# BEE_BOARD_POWER.net
KiCad netlist of a schematic drawn in Altium Designer
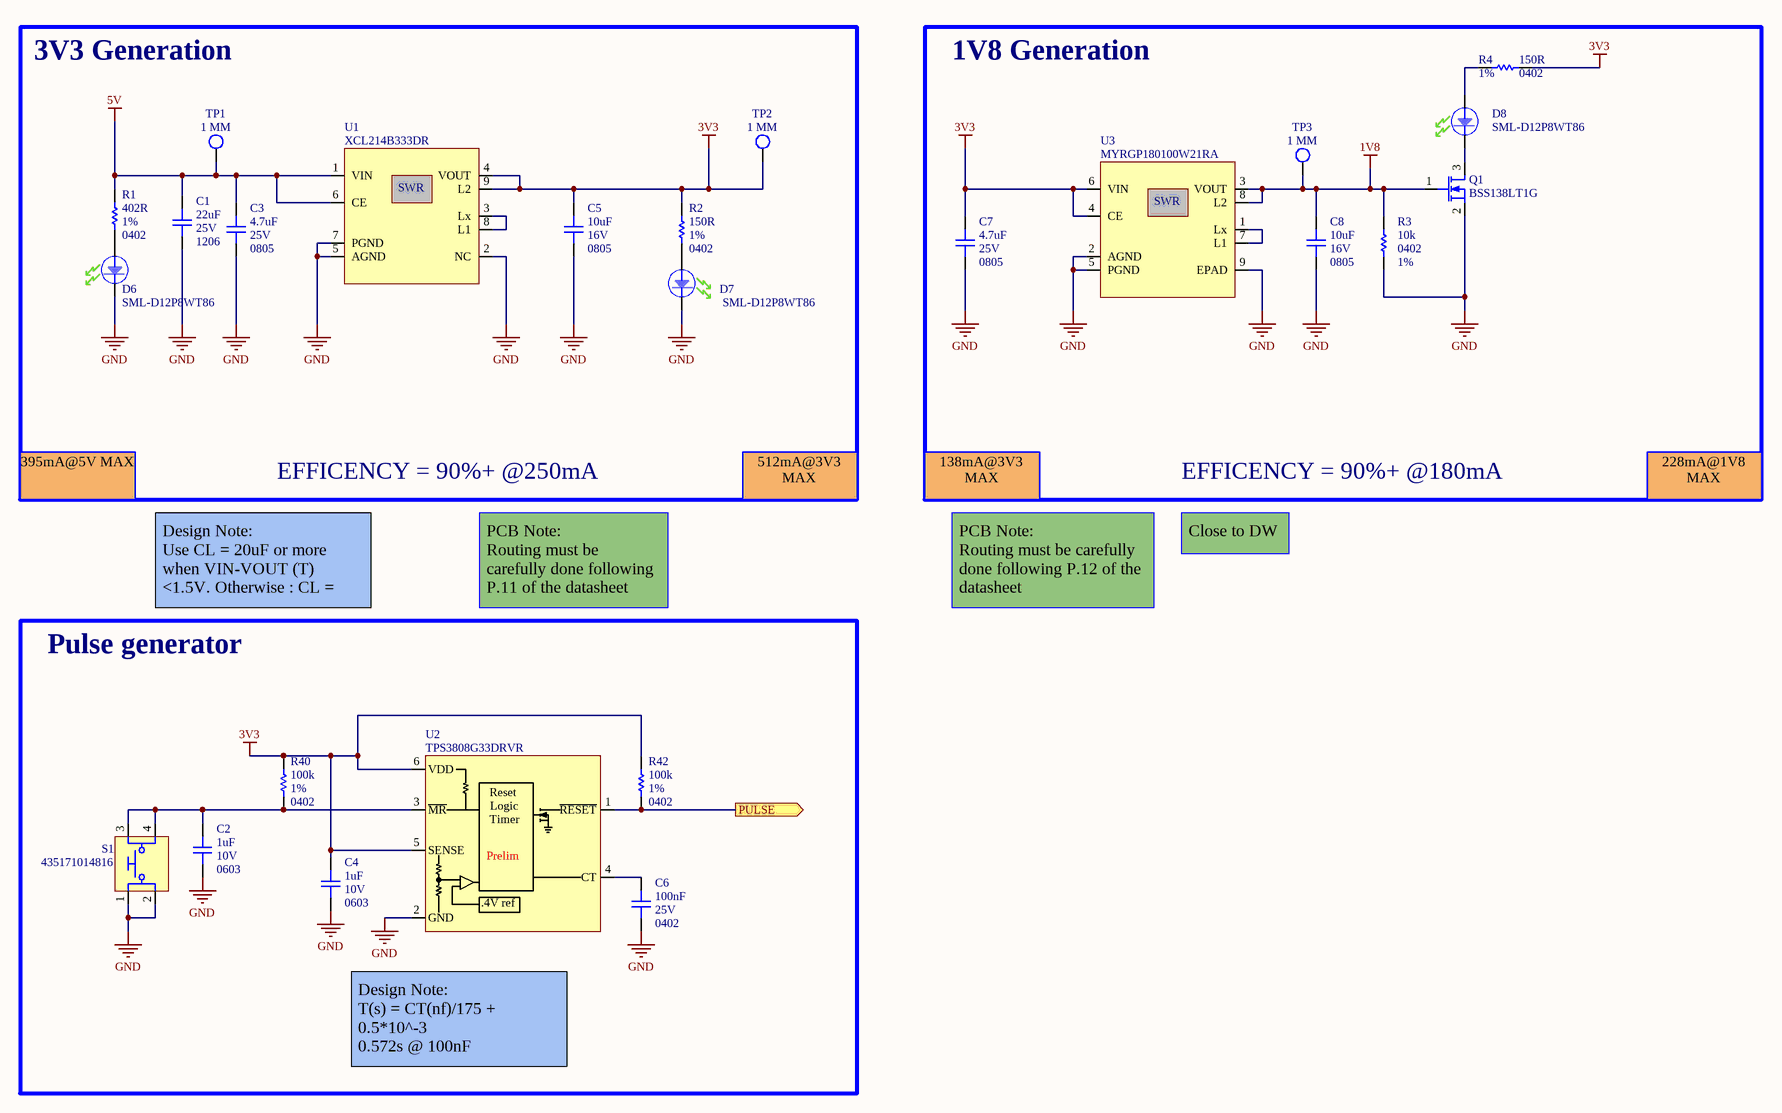
[diagram p0: BEE_BOARD_POWER.SchDoc]

(export (version "E")
  (design (tool "Eeschema 10.0.6"))
  (components
    (comp (ref "C1")
      (value "22uF")
      (footprint "grams_master_lib_pcb:CAP_CER_1206")
      (description "CAP - CER 22uF 10% 25V X5R - 1206")
      (fields
        (field (name "TOLERANCE") "10%")
        (field (name "PACKAGE") "1206")
        (field (name "VOLTAGE RATING") "25V")
        (field (name "Comment") "CL31A226KAHNNNE")
        (field (name "CREATEDBY/DATE") "Philippe Arsenault/21 Janvier 2020")
        (field (name "VERIFIEDBY") "C.Paulin - 28/01/2020")
      )
      (libsource (lib "GRAMS_MASTER_LIB_SCH") (part "CAP_CER_CL31A226KAHNNNE"))
    )
    (comp (ref "C2")
      (value "1uF")
      (footprint "CAP_CER_0603")
      (description "CAP - CER 1uF 10V 10% X5R - 0603")
      (fields
        (field (name "TOLERANCE") "10%")
        (field (name "PACKAGE") "0603")
        (field (name "VOLTAGE RATING") "10V")
        (field (name "Comment") "C0603C105K8PACTU")
        (field (name "CREATEDBY/DATE") "Hubert Dube - 21/07/20")
        (field (name "VERIFIEDBY") "Louis-Daniel Gaulin - 21/07/20")
      )
      (libsource (lib "SWARMUS_LIB") (part "CAP_CER_C0603C105K8PACTU"))
    )
    (comp (ref "C3")
      (value "4.7uF")
      (footprint "GRAMS_MASTER_LIB_PCB:CAP_CER_0805")
      (description "CAP - CER 4.7UF 10% 25V X7R - 0805")
      (fields
        (field (name "TOLERANCE") "10%")
        (field (name "PACKAGE") "0805")
        (field (name "VOLTAGE RATING") "25V")
        (field (name "Comment") "C2012X7R1E475K125AE")
        (field (name "CREATEDBY/DATE") "Keven Deslandes - 2018/11/09")
        (field (name "VERIFIEDBY") "Nicolas Roy - 2018/12/11")
      )
      (libsource (lib "GRAMS_MASTER_LIB_SCH") (part "CAP_CER_C2012X7R1E475K125AE"))
    )
    (comp (ref "C4")
      (value "1uF")
      (footprint "CAP_CER_0603")
      (description "CAP - CER 1uF 10V 10% X5R - 0603")
      (fields
        (field (name "TOLERANCE") "10%")
        (field (name "PACKAGE") "0603")
        (field (name "VOLTAGE RATING") "10V")
        (field (name "Comment") "C0603C105K8PACTU")
        (field (name "CREATEDBY/DATE") "Hubert Dube - 21/07/20")
        (field (name "VERIFIEDBY") "Louis-Daniel Gaulin - 21/07/20")
      )
      (libsource (lib "SWARMUS_LIB") (part "CAP_CER_C0603C105K8PACTU"))
    )
    (comp (ref "C5")
      (value "10uF")
      (footprint "GRAMS_MASTER_LIB_PCB:CAP_CER_0805")
      (description "CAP - CER 10UF 10% 16V X5R - 0805")
      (fields
        (field (name "TOLERANCE") "10%")
        (field (name "PACKAGE") "0805")
        (field (name "VOLTAGE RATING") "16V")
        (field (name "Comment") "GRM21BR61C106KE15K")
        (field (name "CREATEDBY/DATE") "Caroline Paulin / 8 août 2018")
        (field (name "VERIFIEDBY") "Nicolas V. (2019-01-22)")
      )
      (libsource (lib "GRAMS_MASTER_LIB_SCH") (part "CAP_CER_GRM21BR61C106KE15K"))
    )
    (comp (ref "C6")
      (value "100nF")
      (footprint "GRAMS_MASTER_LIB_PCB:CAP_CER_0402")
      (description "CAP - CER 0.1µF 10% 25V X7R - 0402")
      (fields
        (field (name "TOLERANCE") "10%")
        (field (name "PACKAGE") "0402")
        (field (name "VOLTAGE RATING") "25V")
        (field (name "Comment") "CGA2B3X7R1E104K050BB")
        (field (name "CREATEDBY/DATE") "Nicolas Roy 2018-11-07")
        (field (name "VERIFIEDBY") "Nicolas V. (2019-01-22)")
      )
      (libsource (lib "GRAMS_MASTER_LIB_SCH") (part "CAP_CER_CGA2B3X7R1E104K050BB"))
    )
    (comp (ref "C7")
      (value "4.7uF")
      (footprint "GRAMS_MASTER_LIB_PCB:CAP_CER_0805")
      (description "CAP - CER 4.7UF 10% 25V X7R - 0805")
      (fields
        (field (name "TOLERANCE") "10%")
        (field (name "PACKAGE") "0805")
        (field (name "VOLTAGE RATING") "25V")
        (field (name "Comment") "C2012X7R1E475K125AE")
        (field (name "CREATEDBY/DATE") "Keven Deslandes - 2018/11/09")
        (field (name "VERIFIEDBY") "Nicolas Roy - 2018/12/11")
      )
      (libsource (lib "GRAMS_MASTER_LIB_SCH") (part "CAP_CER_C2012X7R1E475K125AE"))
    )
    (comp (ref "C8")
      (value "10uF")
      (footprint "GRAMS_MASTER_LIB_PCB:CAP_CER_0805")
      (description "CAP - CER 10UF 10% 16V X5R - 0805")
      (fields
        (field (name "TOLERANCE") "10%")
        (field (name "PACKAGE") "0805")
        (field (name "VOLTAGE RATING") "16V")
        (field (name "Comment") "GRM21BR61C106KE15K")
        (field (name "CREATEDBY/DATE") "Caroline Paulin / 8 août 2018")
        (field (name "VERIFIEDBY") "Nicolas V. (2019-01-22)")
      )
      (libsource (lib "GRAMS_MASTER_LIB_SCH") (part "CAP_CER_GRM21BR61C106KE15K"))
    )
    (comp (ref "D6")
      (value "SML-D12P8WT86")
      (footprint "GRAMS_MASTER_LIB_PCB:LED_SML-D12P8WT86")
      (description "LED - GREEN DIFFUSED 0603 SMD - 0603")
      (fields
        (field (name "CREATEDBY/DATE") "Keven Deslandes - 2018/11/21")
        (field (name "VERIFIEDBY") "Caroline Paulin - 13 février 2019")
      )
      (libsource (lib "GRAMS_MASTER_LIB_SCH") (part "LED_SML-D12P8WT86"))
    )
    (comp (ref "D7")
      (value "SML-D12P8WT86")
      (footprint "GRAMS_MASTER_LIB_PCB:LED_SML-D12P8WT86")
      (description "LED - GREEN DIFFUSED 0603 SMD - 0603")
      (fields
        (field (name "CREATEDBY/DATE") "Keven Deslandes - 2018/11/21")
        (field (name "VERIFIEDBY") "Caroline Paulin - 13 février 2019")
      )
      (libsource (lib "GRAMS_MASTER_LIB_SCH") (part "LED_SML-D12P8WT86"))
    )
    (comp (ref "D8")
      (value "SML-D12P8WT86")
      (footprint "GRAMS_MASTER_LIB_PCB:LED_SML-D12P8WT86")
      (description "LED - GREEN DIFFUSED 0603 SMD - 0603")
      (fields
        (field (name "CREATEDBY/DATE") "Keven Deslandes - 2018/11/21")
        (field (name "VERIFIEDBY") "Caroline Paulin - 13 février 2019")
      )
      (libsource (lib "GRAMS_MASTER_LIB_SCH") (part "LED_SML-D12P8WT86"))
    )
    (comp (ref "Q1")
      (value "BSS138LT1G")
      (footprint "GRAMS_MASTER_LIB_PCB:TRX_NMOS_BSS138LT1G")
      (description "TRX - NMOS - 50V 200MA - SOT−23-3")
      (fields
        (field (name "CREATEDBY/DATE") "Joel Lemay 2018-06-15")
        (field (name "VERIFIEDBY") "Caroline Paulin - 6 sept 2018")
      )
      (libsource (lib "GRAMS_MASTER_LIB_SCH") (part "TRX_NMOS_BSS138LT1G"))
    )
    (comp (ref "R1")
      (value "402R")
      (footprint "GRAMS_MASTER_LIB_PCB:RES_0402")
      (description "RES - 402R 1% 1/10W - 0402")
      (fields
        (field (name "TOLERANCE") "1%")
        (field (name "PACKAGE") "0402")
        (field (name "Comment") "ERJ-2RKF4020X")
        (field (name "CREATEDBY/DATE") "Keven Deslandes 2018-09-20")
        (field (name "VERIFIEDBY") "Caroline Paulin - 18/12/2018")
      )
      (libsource (lib "GRAMS_MASTER_LIB_SCH") (part "RES_ERJ-2RKF4020X"))
    )
    (comp (ref "R2")
      (value "150R")
      (footprint "RES_0402")
      (description "RES - 150R 1% 1/16W - 0402")
      (fields
        (field (name "TOLERANCE") "1%")
        (field (name "PACKAGE") "0402")
        (field (name "Comment") "RC0402FR-07150RL")
        (field (name "CREATEDBY/DATE") "Jonathan Bouchard 2019-03-25")
        (field (name "VERIFIEDBY") "Nicolas V. (2019-05-02)")
      )
      (libsource (lib "GRAMS_MASTER_LIB_SCH") (part "RES_RC0402FR-07150RL"))
    )
    (comp (ref "R3")
      (value "10k")
      (footprint "GRAMS_MASTER_LIB_PCB:RES_0402")
      (description "RES - 10K OHMS 1% 1/16W - 0402")
      (fields
        (field (name "TOLERANCE") "1%")
        (field (name "PACKAGE") "0402")
        (field (name "Comment") "RC0402FR-0710KL")
        (field (name "CREATEDBY/DATE") "Nicolas V. (2018-11-20)")
        (field (name "VERIFIEDBY") "Nicolas V. (2018-11-20)")
      )
      (libsource (lib "GRAMS_MASTER_LIB_SCH") (part "RES_RC0402FR-0710KL"))
    )
    (comp (ref "R4")
      (value "150R")
      (footprint "RES_0402")
      (description "RES - 150R 1% 1/16W - 0402")
      (fields
        (field (name "TOLERANCE") "1%")
        (field (name "PACKAGE") "0402")
        (field (name "Comment") "RC0402FR-07150RL")
        (field (name "CREATEDBY/DATE") "Jonathan Bouchard 2019-03-25")
        (field (name "VERIFIEDBY") "Nicolas V. (2019-05-02)")
      )
      (libsource (lib "GRAMS_MASTER_LIB_SCH") (part "RES_RC0402FR-07150RL"))
    )
    (comp (ref "R40")
      (value "100k")
      (footprint "GRAMS_MASTER_LIB_PCB:RES_0402")
      (description "RES - 100K 1% 1/16W - 0402")
      (fields
        (field (name "TOLERANCE") "1%")
        (field (name "PACKAGE") "0402")
        (field (name "Comment") "RC0402FR-07100KL")
        (field (name "CREATEDBY/DATE") "Keven Deslandes 2018-10-19")
        (field (name "VERIFIEDBY") "Caroline Paulin - 18/12/2018")
      )
      (libsource (lib "GRAMS_MASTER_LIB_SCH") (part "RES_RC0402FR-07100KL"))
    )
    (comp (ref "R42")
      (value "100k")
      (footprint "GRAMS_MASTER_LIB_PCB:RES_0402")
      (description "RES - 100K 1% 1/16W - 0402")
      (fields
        (field (name "TOLERANCE") "1%")
        (field (name "PACKAGE") "0402")
        (field (name "Comment") "RC0402FR-07100KL")
        (field (name "CREATEDBY/DATE") "Keven Deslandes 2018-10-19")
        (field (name "VERIFIEDBY") "Caroline Paulin - 18/12/2018")
      )
      (libsource (lib "GRAMS_MASTER_LIB_SCH") (part "RES_RC0402FR-07100KL"))
    )
    (comp (ref "S1")
      (value "435171014816")
      (footprint "SWI_TACT_435171014816")
      (description "SWI - SWITCH TACTILE SPST-NO 0.05A 12V -SMD")
      (fields
        (field (name "CREATEDBY/DATE") "Hubert Dube - 22/07/20")
        (field (name "VERIFIEDBY") "Louis-Daniel Gaulin / 12-11-2020")
      )
      (libsource (lib "SWARMUS_LIB") (part "SWI_TACT_435171014816"))
    )
    (comp (ref "TP1")
      (value "1 MM")
      (footprint "GRAMS_MASTER_LIB_PCB:TPO_SMD_ROUND_1MM")
      (description "TPO - TEST POINT ROUND SMD PAD ONLY  - 1 MM")
      (fields
        (field (name "CREATEDBY/DATE") "Jonathan Bouchard 2018-07-17")
        (field (name "VERIFIEDBY") "Arnaud Samson 23-07-18")
      )
      (libsource (lib "GRAMS_MASTER_LIB_SCH") (part "TPO_SMD_ROUND_1MM"))
    )
    (comp (ref "TP2")
      (value "1 MM")
      (footprint "GRAMS_MASTER_LIB_PCB:TPO_SMD_ROUND_1MM")
      (description "TPO - TEST POINT ROUND SMD PAD ONLY  - 1 MM")
      (fields
        (field (name "CREATEDBY/DATE") "Jonathan Bouchard 2018-07-17")
        (field (name "VERIFIEDBY") "Arnaud Samson 23-07-18")
      )
      (libsource (lib "GRAMS_MASTER_LIB_SCH") (part "TPO_SMD_ROUND_1MM"))
    )
    (comp (ref "TP3")
      (value "1 MM")
      (footprint "GRAMS_MASTER_LIB_PCB:TPO_SMD_ROUND_1MM")
      (description "TPO - TEST POINT ROUND SMD PAD ONLY  - 1 MM")
      (fields
        (field (name "CREATEDBY/DATE") "Jonathan Bouchard 2018-07-17")
        (field (name "VERIFIEDBY") "Arnaud Samson 23-07-18")
      )
      (libsource (lib "GRAMS_MASTER_LIB_SCH") (part "TPO_SMD_ROUND_1MM"))
    )
    (comp (ref "U1")
      (value "XCL214B333DR")
      (footprint "REG_SWR_XCL214B333DR")
      (description "REG_DC DC CONVERTER 3.3V 5W_9-PowerTFQFN")
      (fields
        (field (name "CREATEDBY/DATE") "Louis-Daniel Gaulin / 21-07-2020")
        (field (name "VERIFIEDBY") "Philippe Arsenault/2020-11-06")
      )
      (libsource (lib "SWARMUS_LIB") (part "REG_SWR_XCL214B333DR"))
    )
    (comp (ref "U2")
      (value "TPS3808G33DRVR")
      (footprint "POW_TPS3808G33DRVR")
      (description "POW - Programmable-Delay Supervisory Circuit - 6WSON")
      (fields (field (name "CREATEDBY/DATE") "Philippe Arsenault/2021-04-19"))
      (libsource (lib "a_Valider_PA") (part "POW_TPS3808G33DRVR"))
    )
    (comp (ref "U3")
      (value "MYRGP180100W21RA")
      (footprint "REG_SWR_MYRGP180100W21RA")
      (description "REG_DC DC CONVERTER 1.8V 1.8W_8-PowerTDFN")
      (fields
        (field (name "CREATEDBY/DATE") "Louis-Daniel Gaulin / 21-07-2020")
        (field (name "VERIFIEDBY") "Philippe Arsenault/2020-11-06")
      )
      (libsource (lib "SWARMUS_LIB") (part "REG_SWR_MYRGP180100W21RA"))
    )
  )
  (nets
    (net (code "1") (name "/PULSE") (class "Default")
      (node (ref "R42") (pin "1") (pinfunction "1_1") (pintype "passive"))
      (node (ref "U2") (pin "1") (pinfunction "~{RESET}_1") (pintype "passive"))
    )
    (net (code "2") (name "1V8") (class "Default")
      (node (ref "C8") (pin "2") (pinfunction "2_2") (pintype "passive"))
      (node (ref "Q1") (pin "1") (pinfunction "G_1") (pintype "passive"))
      (node (ref "R3") (pin "1") (pinfunction "1_1") (pintype "passive"))
      (node (ref "TP3") (pin "1") (pinfunction "1_1") (pintype "passive"))
      (node (ref "U3") (pin "3") (pinfunction "VOUT_3") (pintype "passive"))
      (node (ref "U3") (pin "8") (pinfunction "L2_8") (pintype "passive"))
    )
    (net (code "3") (name "3V3") (class "Default")
      (node (ref "C4") (pin "1") (pinfunction "1_1") (pintype "passive"))
      (node (ref "C5") (pin "2") (pinfunction "2_2") (pintype "passive"))
      (node (ref "C7") (pin "2") (pinfunction "2_2") (pintype "passive"))
      (node (ref "R2") (pin "2") (pinfunction "2_2") (pintype "passive"))
      (node (ref "R4") (pin "1") (pinfunction "1_1") (pintype "passive"))
      (node (ref "R40") (pin "2") (pinfunction "2_2") (pintype "passive"))
      (node (ref "R42") (pin "2") (pinfunction "2_2") (pintype "passive"))
      (node (ref "TP2") (pin "1") (pinfunction "1_1") (pintype "passive"))
      (node (ref "U1") (pin "4") (pinfunction "VOUT_4") (pintype "passive"))
      (node (ref "U1") (pin "9") (pinfunction "L2_9") (pintype "passive"))
      (node (ref "U2") (pin "5") (pinfunction "SENSE_5") (pintype "passive"))
      (node (ref "U2") (pin "6") (pinfunction "VDD_6") (pintype "passive"))
      (node (ref "U3") (pin "4") (pinfunction "CE_4") (pintype "passive"))
      (node (ref "U3") (pin "6") (pinfunction "VIN_6") (pintype "passive"))
    )
    (net (code "4") (name "5V") (class "Default")
      (node (ref "C1") (pin "2") (pinfunction "2_2") (pintype "passive"))
      (node (ref "C3") (pin "2") (pinfunction "2_2") (pintype "passive"))
      (node (ref "R1") (pin "2") (pinfunction "2_2") (pintype "passive"))
      (node (ref "TP1") (pin "1") (pinfunction "1_1") (pintype "passive"))
      (node (ref "U1") (pin "1") (pinfunction "VIN_1") (pintype "passive"))
      (node (ref "U1") (pin "6") (pinfunction "CE_6") (pintype "passive"))
    )
    (net (code "5") (name "GND") (class "Default")
      (node (ref "C1") (pin "1") (pinfunction "1_1") (pintype "passive"))
      (node (ref "C2") (pin "2") (pinfunction "2_2") (pintype "passive"))
      (node (ref "C3") (pin "1") (pinfunction "1_1") (pintype "passive"))
      (node (ref "C4") (pin "2") (pinfunction "2_2") (pintype "passive"))
      (node (ref "C5") (pin "1") (pinfunction "1_1") (pintype "passive"))
      (node (ref "C6") (pin "1") (pinfunction "1_1") (pintype "passive"))
      (node (ref "C7") (pin "1") (pinfunction "1_1") (pintype "passive"))
      (node (ref "C8") (pin "1") (pinfunction "1_1") (pintype "passive"))
      (node (ref "D6") (pin "K") (pinfunction "K_K") (pintype "passive"))
      (node (ref "D7") (pin "K") (pinfunction "K_K") (pintype "passive"))
      (node (ref "Q1") (pin "2") (pinfunction "S_2") (pintype "passive"))
      (node (ref "R3") (pin "2") (pinfunction "2_2") (pintype "passive"))
      (node (ref "S1") (pin "1") (pinfunction "1_1") (pintype "passive"))
      (node (ref "S1") (pin "2") (pinfunction "2_2") (pintype "passive"))
      (node (ref "U1") (pin "2") (pinfunction "NC_2") (pintype "passive"))
      (node (ref "U1") (pin "5") (pinfunction "AGND_5") (pintype "passive"))
      (node (ref "U1") (pin "7") (pinfunction "PGND_7") (pintype "passive"))
      (node (ref "U2") (pin "2") (pinfunction "GND_2") (pintype "passive"))
      (node (ref "U3") (pin "2") (pinfunction "AGND_2") (pintype "passive"))
      (node (ref "U3") (pin "5") (pinfunction "PGND_5") (pintype "passive"))
      (node (ref "U3") (pin "9") (pinfunction "EPAD_9") (pintype "passive"))
    )
    (net (code "6") (name "Net-(D6-PadA)") (class "Default")
      (node (ref "D6") (pin "A") (pinfunction "A_A") (pintype "passive"))
      (node (ref "R1") (pin "1") (pinfunction "1_1") (pintype "passive"))
    )
    (net (code "7") (name "Net-(D7-PadA)") (class "Default")
      (node (ref "D7") (pin "A") (pinfunction "A_A") (pintype "passive"))
      (node (ref "R2") (pin "1") (pinfunction "1_1") (pintype "passive"))
    )
    (net (code "8") (name "Net-(D8-PadA)") (class "Default")
      (node (ref "D8") (pin "A") (pinfunction "A_A") (pintype "passive"))
      (node (ref "R4") (pin "2") (pinfunction "2_2") (pintype "passive"))
    )
    (net (code "9") (name "Net-(Q1-D)") (class "Default")
      (node (ref "D8") (pin "K") (pinfunction "K_K") (pintype "passive"))
      (node (ref "Q1") (pin "3") (pinfunction "D_3") (pintype "passive"))
    )
    (net (code "10") (name "Net-(U1-L1)") (class "Default")
      (node (ref "U1") (pin "3") (pinfunction "Lx_3") (pintype "passive"))
      (node (ref "U1") (pin "8") (pinfunction "L1_8") (pintype "passive"))
    )
    (net (code "11") (name "Net-(U2-CT)") (class "Default")
      (node (ref "C6") (pin "2") (pinfunction "2_2") (pintype "passive"))
      (node (ref "U2") (pin "4") (pinfunction "CT_4") (pintype "passive"))
    )
    (net (code "12") (name "Net-(U2-~{MR})") (class "Default")
      (node (ref "C2") (pin "1") (pinfunction "1_1") (pintype "passive"))
      (node (ref "R40") (pin "1") (pinfunction "1_1") (pintype "passive"))
      (node (ref "S1") (pin "3") (pinfunction "3_3") (pintype "passive"))
      (node (ref "S1") (pin "4") (pinfunction "4_4") (pintype "passive"))
      (node (ref "U2") (pin "3") (pinfunction "~{MR}_3") (pintype "passive"))
    )
    (net (code "13") (name "Net-(U3-L1)") (class "Default")
      (node (ref "U3") (pin "1") (pinfunction "Lx_1") (pintype "passive"))
      (node (ref "U3") (pin "7") (pinfunction "L1_7") (pintype "passive"))
    )
  )
)
